# SolenoidSwitching.net
KiCad netlist of a schematic drawn in Altium Designer
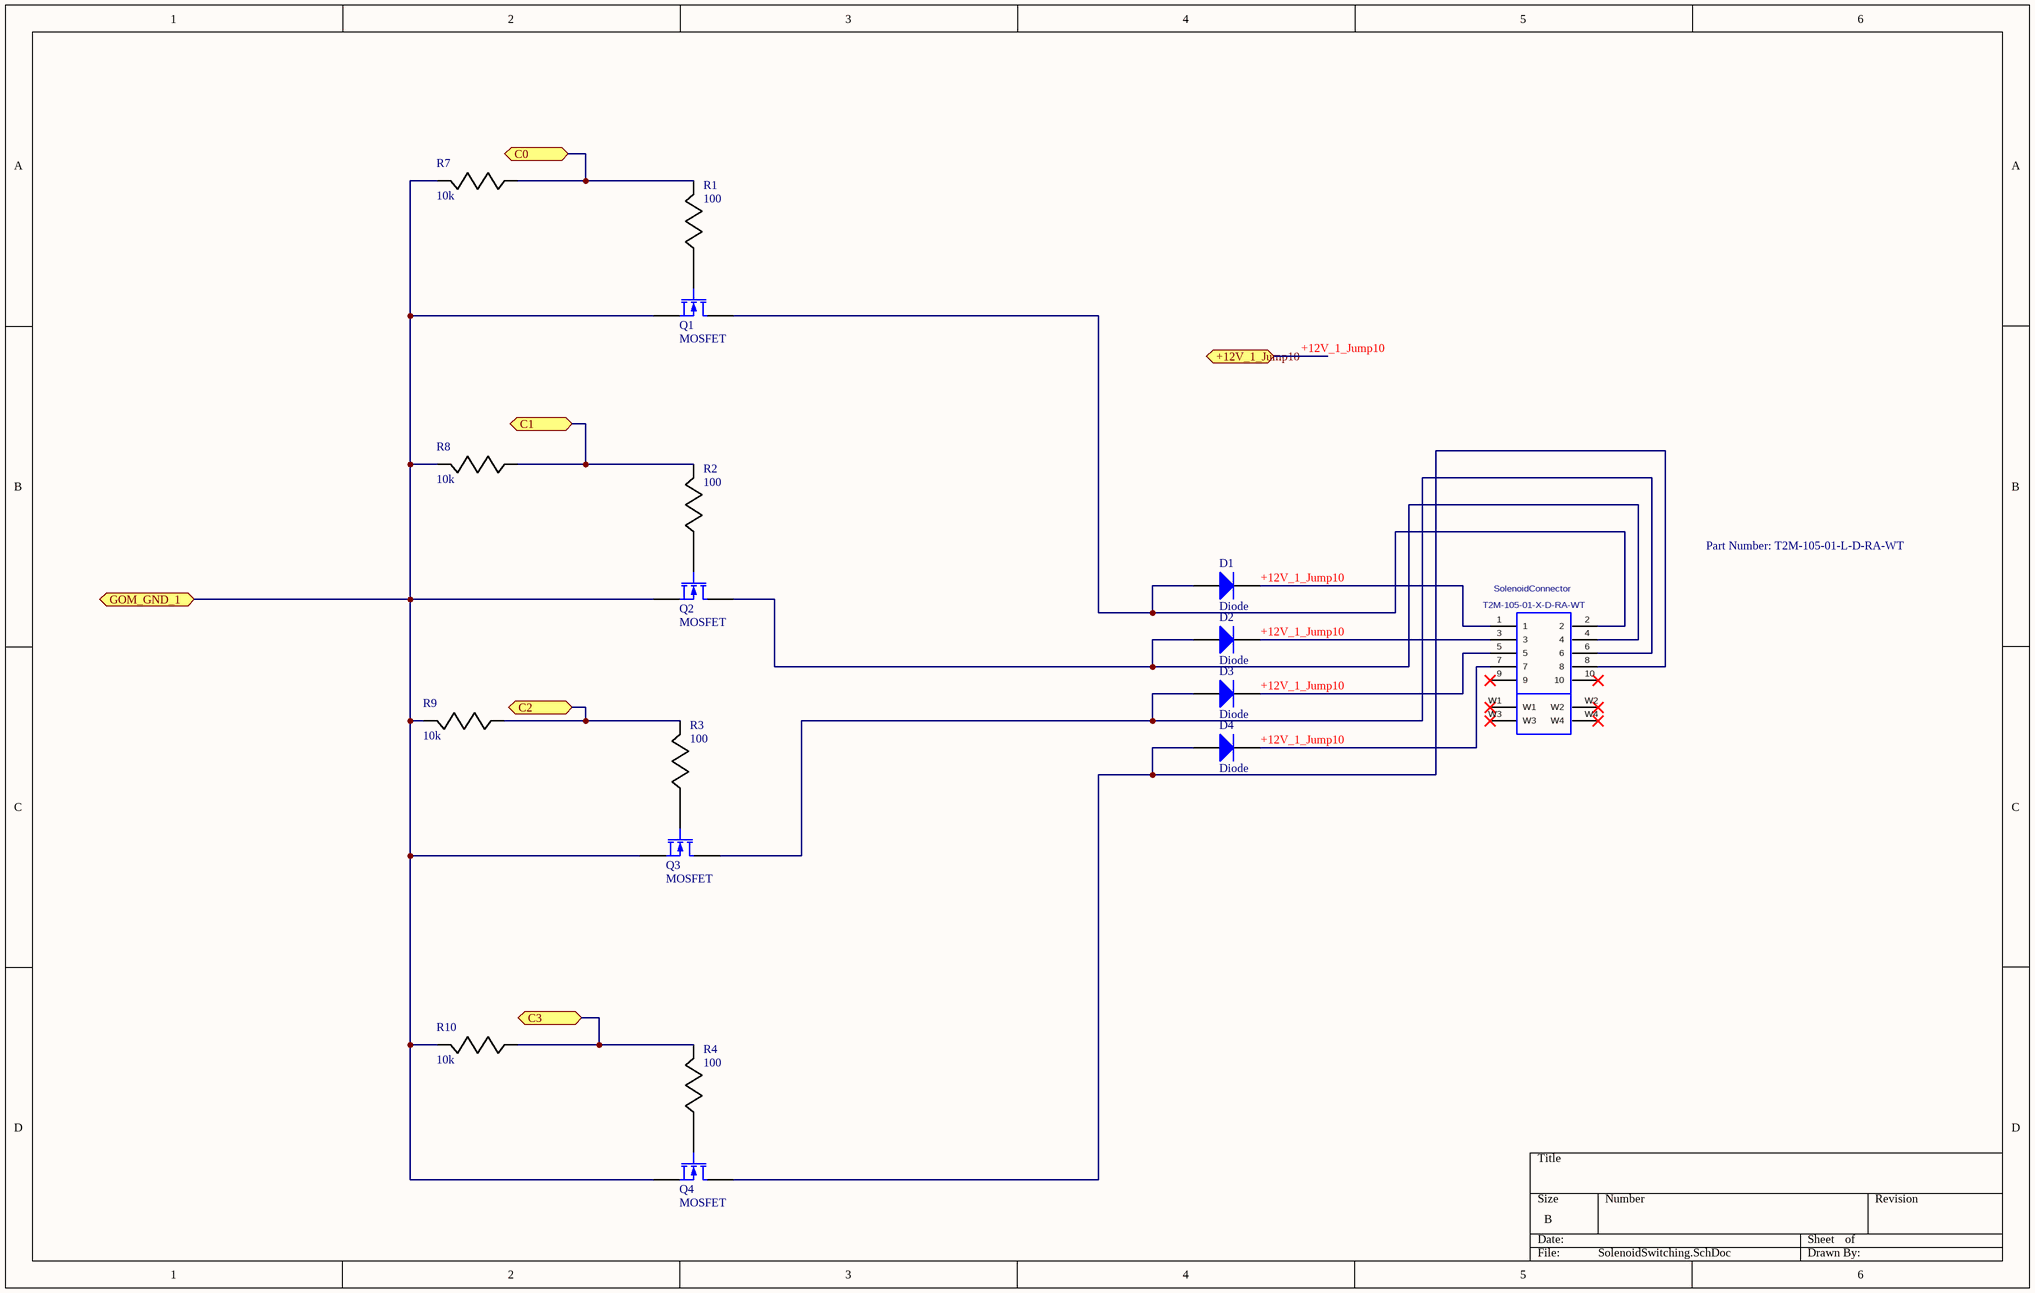
[diagram p0: SolenoidSwitching.SchDoc]

(export (version "E")
  (design (tool "Eeschema 10.0.6"))
  (components
    (comp (ref "D1")
      (value "Diode")
      (footprint "SMC")
      (description "Default Diode")
      (fields (field (name "PUBLISHER") "Altium Limited"))
      (libsource (lib "Miscellaneous Devices") (part "Diode"))
    )
    (comp (ref "D2")
      (value "Diode")
      (footprint "SMC")
      (description "Default Diode")
      (fields (field (name "PUBLISHER") "Altium Limited"))
      (libsource (lib "Miscellaneous Devices") (part "Diode"))
    )
    (comp (ref "D3")
      (value "Diode")
      (footprint "SMC")
      (description "Default Diode")
      (fields (field (name "PUBLISHER") "Altium Limited"))
      (libsource (lib "Miscellaneous Devices") (part "Diode"))
    )
    (comp (ref "D4")
      (value "Diode")
      (footprint "SMC")
      (description "Default Diode")
      (fields (field (name "PUBLISHER") "Altium Limited"))
      (libsource (lib "Miscellaneous Devices") (part "Diode"))
    )
    (comp (ref "Q1")
      (value "MOSFET")
      (footprint "TO-226-AA")
      (description "N-Channel MOSFET")
      (fields (field (name "PUBLISHER") "Altium Limited"))
      (libsource (lib "Miscellaneous Devices") (part "MOSFET-N"))
    )
    (comp (ref "Q2")
      (value "MOSFET")
      (footprint "TO-226-AA")
      (description "N-Channel MOSFET")
      (fields (field (name "PUBLISHER") "Altium Limited"))
      (libsource (lib "Miscellaneous Devices") (part "MOSFET-N"))
    )
    (comp (ref "Q3")
      (value "MOSFET")
      (footprint "TO-226-AA")
      (description "N-Channel MOSFET")
      (fields (field (name "PUBLISHER") "Altium Limited"))
      (libsource (lib "Miscellaneous Devices") (part "MOSFET-N"))
    )
    (comp (ref "Q4")
      (value "MOSFET")
      (footprint "TO-226-AA")
      (description "N-Channel MOSFET")
      (fields (field (name "PUBLISHER") "Altium Limited"))
      (libsource (lib "Miscellaneous Devices") (part "MOSFET-N"))
    )
    (comp (ref "R1")
      (value "100")
      (footprint "AXIAL-0.3")
      (description "Imported")
      (fields (field (name "MANUFACTURER_PART_NUMBER") "PMR100HZPFU6L00"))
      (libsource (lib "2016-03-26_18-23-46") (part "PMR100HZPFU6L00"))
    )
    (comp (ref "R2")
      (value "100")
      (footprint "AXIAL-0.3")
      (description "Imported")
      (fields (field (name "MANUFACTURER_PART_NUMBER") "PMR100HZPFU6L00"))
      (libsource (lib "2016-03-26_18-23-46") (part "PMR100HZPFU6L00"))
    )
    (comp (ref "R3")
      (value "100")
      (footprint "AXIAL-0.3")
      (description "Imported")
      (fields (field (name "MANUFACTURER_PART_NUMBER") "PMR100HZPFU6L00"))
      (libsource (lib "2016-03-26_18-23-46") (part "PMR100HZPFU6L00"))
    )
    (comp (ref "R4")
      (value "100")
      (footprint "AXIAL-0.3")
      (description "Imported")
      (fields (field (name "MANUFACTURER_PART_NUMBER") "PMR100HZPFU6L00"))
      (libsource (lib "2016-03-26_18-23-46") (part "PMR100HZPFU6L00"))
    )
    (comp (ref "R7")
      (value "10k")
      (footprint "AXIAL-0.3")
      (description "Imported")
      (fields (field (name "MANUFACTURER_PART_NUMBER") "PMR100HZPFU6L00"))
      (libsource (lib "2016-03-26_18-23-46") (part "PMR100HZPFU6L00"))
    )
    (comp (ref "R8")
      (value "10k")
      (footprint "AXIAL-0.3")
      (description "Imported")
      (fields (field (name "MANUFACTURER_PART_NUMBER") "PMR100HZPFU6L00"))
      (libsource (lib "2016-03-26_18-23-46") (part "PMR100HZPFU6L00"))
    )
    (comp (ref "R9")
      (value "10k")
      (footprint "AXIAL-0.3")
      (description "Imported")
      (fields (field (name "MANUFACTURER_PART_NUMBER") "PMR100HZPFU6L00"))
      (libsource (lib "2016-03-26_18-23-46") (part "PMR100HZPFU6L00"))
    )
    (comp (ref "R10")
      (value "10k")
      (footprint "AXIAL-0.3")
      (description "Imported")
      (fields (field (name "MANUFACTURER_PART_NUMBER") "PMR100HZPFU6L00"))
      (libsource (lib "2016-03-26_18-23-46") (part "PMR100HZPFU6L00"))
    )
    (comp (ref "SolenoidConnector")
      (value "T2M-105-01-X-D-RA-WT")
      (footprint "T2M-105-01-X-D-RA-WT")
      (description "2MM PITCH SHROUDED RIGHT ANGLE TERMINAL STRIP.")
      (fields
        (field (name "MANUFACTURER") "SAMTEC")
        (field (name "CREATED") "September 24, 2014 - Wendy Xin")
      )
      (libsource (lib "T2M-105-01-X-D-RA-WT") (part "T2M-105-01-X-D-RA-WT"))
    )
  )
  (nets
    (net (code "1") (name "/+12V_1_Jump10") (class "Default")
      (node (ref "D1") (pin "2") (pinfunction "K_2") (pintype "passive"))
      (node (ref "D2") (pin "2") (pinfunction "K_2") (pintype "passive"))
      (node (ref "D3") (pin "2") (pinfunction "K_2") (pintype "passive"))
      (node (ref "D4") (pin "2") (pinfunction "K_2") (pintype "passive"))
      (node (ref "SolenoidConnector") (pin "1") (pinfunction "1_1") (pintype "passive"))
      (node (ref "SolenoidConnector") (pin "3") (pinfunction "3_3") (pintype "passive"))
      (node (ref "SolenoidConnector") (pin "5") (pinfunction "5_5") (pintype "passive"))
      (node (ref "SolenoidConnector") (pin "7") (pinfunction "7_7") (pintype "passive"))
    )
    (net (code "2") (name "/C0") (class "Default")
      (node (ref "R1") (pin "1") (pinfunction "1_1") (pintype "passive"))
      (node (ref "R7") (pin "2") (pinfunction "2_2") (pintype "passive"))
    )
    (net (code "3") (name "/C1") (class "Default")
      (node (ref "R2") (pin "1") (pinfunction "1_1") (pintype "passive"))
      (node (ref "R8") (pin "2") (pinfunction "2_2") (pintype "passive"))
    )
    (net (code "4") (name "/C2") (class "Default")
      (node (ref "R3") (pin "1") (pinfunction "1_1") (pintype "passive"))
      (node (ref "R9") (pin "2") (pinfunction "2_2") (pintype "passive"))
    )
    (net (code "5") (name "/C3") (class "Default")
      (node (ref "R10") (pin "2") (pinfunction "2_2") (pintype "passive"))
      (node (ref "R4") (pin "1") (pinfunction "1_1") (pintype "passive"))
    )
    (net (code "6") (name "/GOM_GND_1") (class "Default")
      (node (ref "Q1") (pin "3") (pinfunction "S_3") (pintype "passive"))
      (node (ref "Q2") (pin "3") (pinfunction "S_3") (pintype "passive"))
      (node (ref "Q3") (pin "3") (pinfunction "S_3") (pintype "passive"))
      (node (ref "Q4") (pin "3") (pinfunction "S_3") (pintype "passive"))
      (node (ref "R10") (pin "1") (pinfunction "1_1") (pintype "passive"))
      (node (ref "R7") (pin "1") (pinfunction "1_1") (pintype "passive"))
      (node (ref "R8") (pin "1") (pinfunction "1_1") (pintype "passive"))
      (node (ref "R9") (pin "1") (pinfunction "1_1") (pintype "passive"))
    )
    (net (code "7") (name "Net-(D1-A)") (class "Default")
      (node (ref "D1") (pin "1") (pinfunction "A_1") (pintype "passive"))
      (node (ref "Q1") (pin "1") (pinfunction "D_1") (pintype "passive"))
      (node (ref "SolenoidConnector") (pin "2") (pinfunction "2_2") (pintype "passive"))
    )
    (net (code "8") (name "Net-(D2-A)") (class "Default")
      (node (ref "D2") (pin "1") (pinfunction "A_1") (pintype "passive"))
      (node (ref "Q2") (pin "1") (pinfunction "D_1") (pintype "passive"))
      (node (ref "SolenoidConnector") (pin "4") (pinfunction "4_4") (pintype "passive"))
    )
    (net (code "9") (name "Net-(D3-A)") (class "Default")
      (node (ref "D3") (pin "1") (pinfunction "A_1") (pintype "passive"))
      (node (ref "Q3") (pin "1") (pinfunction "D_1") (pintype "passive"))
      (node (ref "SolenoidConnector") (pin "6") (pinfunction "6_6") (pintype "passive"))
    )
    (net (code "10") (name "Net-(D4-A)") (class "Default")
      (node (ref "D4") (pin "1") (pinfunction "A_1") (pintype "passive"))
      (node (ref "Q4") (pin "1") (pinfunction "D_1") (pintype "passive"))
      (node (ref "SolenoidConnector") (pin "8") (pinfunction "8_8") (pintype "passive"))
    )
    (net (code "11") (name "Net-(Q1-G)") (class "Default")
      (node (ref "Q1") (pin "2") (pinfunction "G_2") (pintype "passive"))
      (node (ref "R1") (pin "2") (pinfunction "2_2") (pintype "passive"))
    )
    (net (code "12") (name "Net-(Q2-G)") (class "Default")
      (node (ref "Q2") (pin "2") (pinfunction "G_2") (pintype "passive"))
      (node (ref "R2") (pin "2") (pinfunction "2_2") (pintype "passive"))
    )
    (net (code "13") (name "Net-(Q3-G)") (class "Default")
      (node (ref "Q3") (pin "2") (pinfunction "G_2") (pintype "passive"))
      (node (ref "R3") (pin "2") (pinfunction "2_2") (pintype "passive"))
    )
    (net (code "14") (name "Net-(Q4-G)") (class "Default")
      (node (ref "Q4") (pin "2") (pinfunction "G_2") (pintype "passive"))
      (node (ref "R4") (pin "2") (pinfunction "2_2") (pintype "passive"))
    )
    (net (code "15") (name "unconnected-(SolenoidConnector-Pad9)") (class "Default")
      (node (ref "SolenoidConnector") (pin "9") (pinfunction "9_9") (pintype "passive+no_connect"))
    )
    (net (code "16") (name "unconnected-(SolenoidConnector-Pad10)") (class "Default")
      (node (ref "SolenoidConnector") (pin "10") (pinfunction "10_10") (pintype "passive+no_connect"))
    )
    (net (code "17") (name "unconnected-(SolenoidConnector-PadW1)") (class "Default")
      (node (ref "SolenoidConnector") (pin "W1") (pinfunction "W1_W1") (pintype "passive+no_connect"))
    )
    (net (code "18") (name "unconnected-(SolenoidConnector-PadW2)") (class "Default")
      (node (ref "SolenoidConnector") (pin "W2") (pinfunction "W2_W2") (pintype "passive+no_connect"))
    )
    (net (code "19") (name "unconnected-(SolenoidConnector-PadW3)") (class "Default")
      (node (ref "SolenoidConnector") (pin "W3") (pinfunction "W3_W3") (pintype "passive+no_connect"))
    )
    (net (code "20") (name "unconnected-(SolenoidConnector-PadW4)") (class "Default")
      (node (ref "SolenoidConnector") (pin "W4") (pinfunction "W4_W4") (pintype "passive+no_connect"))
    )
  )
)
